# Barometer.net
KiCad netlist of a schematic drawn in Altium Designer
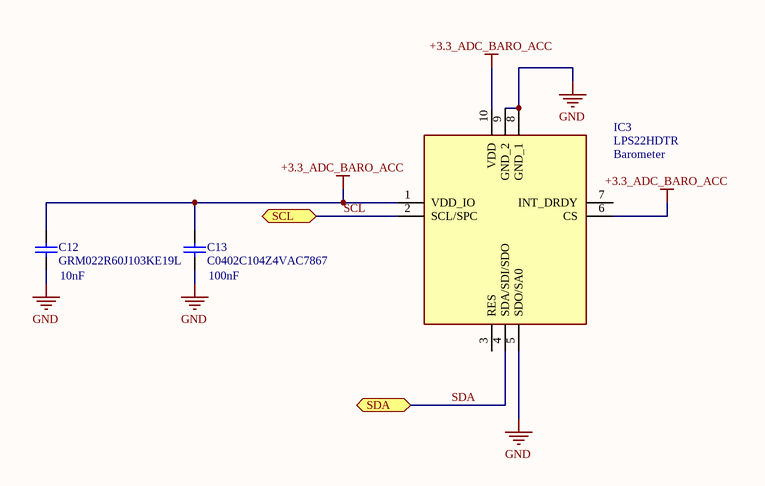
[diagram p0: Barometer.SchDoc]

(export (version "E")
  (design (tool "Eeschema 10.0.6"))
  (components
    (comp (ref "C12")
      (value "GRM022R60J103KE19L")
      (footprint "CAPC1005X55X25NL05T10")
      (fields (field (name "MANUFACTURER") "Murata") (field (name "SPEC") "10nF"))
      (libsource (lib "Altium Content Vault") (part "CAP"))
    )
    (comp (ref "C13")
      (value "C0402C104Z4VAC7867")
      (footprint "CAPC1005X60X30LL05T10")
      (fields (field (name "MANUFACTURER") "Kemet") (field (name "SPEC") "100nF"))
      (libsource (lib "Altium Content Vault") (part "CAP"))
    )
    (comp (ref "IC3")
      (value "LPS22HDTR")
      (footprint "PcbLib1:LPS22HDTR")
      (description "Integrated Circuit")
      (fields (field (name "MOUSER PART NUMBER") "511-LPS22HDTR"))
      (libsource (lib "*") (part "LPS22HDTR"))
    )
  )
  (nets
    (net (code "1") (name "+3.3_ADC_BARO_ACC") (class "Default")
      (node (ref "C12") (pin "2") (pinfunction "2_2") (pintype "passive"))
      (node (ref "C13") (pin "2") (pinfunction "2_2") (pintype "passive"))
      (node (ref "IC3") (pin "1") (pinfunction "VDD_IO_1") (pintype "passive"))
      (node (ref "IC3") (pin "10") (pinfunction "VDD_10") (pintype "passive"))
      (node (ref "IC3") (pin "6") (pinfunction "CS_6") (pintype "passive"))
    )
    (net (code "2") (name "/SCL") (class "Default")
      (node (ref "IC3") (pin "2") (pinfunction "SCL/SPC_2") (pintype "passive"))
    )
    (net (code "3") (name "/SDA") (class "Default")
      (node (ref "IC3") (pin "4") (pinfunction "SDA/SDI/SDO_4") (pintype "passive"))
    )
    (net (code "4") (name "GND") (class "Default")
      (node (ref "C12") (pin "1") (pinfunction "1_1") (pintype "passive"))
      (node (ref "C13") (pin "1") (pinfunction "1_1") (pintype "passive"))
      (node (ref "IC3") (pin "5") (pinfunction "SDO/SA0_5") (pintype "passive"))
      (node (ref "IC3") (pin "8") (pinfunction "GND_1_8") (pintype "passive"))
      (node (ref "IC3") (pin "9") (pinfunction "GND_2_9") (pintype "passive"))
    )
    (net (code "5") (name "unconnected-(IC3-INT_DRDY-Pad7)") (class "Default")
      (node (ref "IC3") (pin "7") (pinfunction "INT_DRDY_7") (pintype "passive"))
    )
    (net (code "6") (name "unconnected-(IC3-RES-Pad3)") (class "Default")
      (node (ref "IC3") (pin "3") (pinfunction "RES_3") (pintype "passive"))
    )
  )
)
